# design.net
KiCad netlist of a schematic drawn in Altium Designer
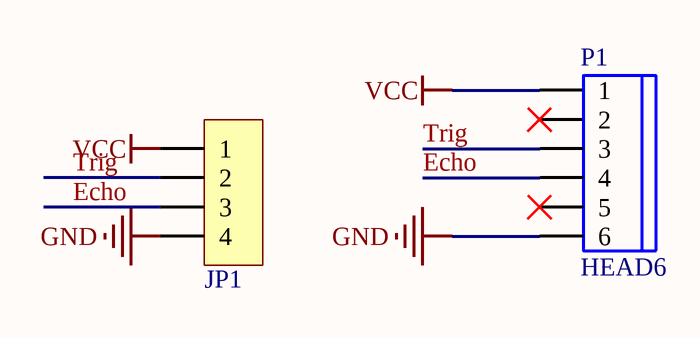
[diagram p0: 超声波模块云台原理图.SchDoc]

(export (version "E")
  (design (tool "Eeschema 10.0.6"))
  (components
    (comp (ref "JP1")
      (value "HDR-1X4")
      (footprint "HDR2.54-LI-4P")
      (description "4P接插件")
      (fields (field (name "版权归属") "封装库来自淘宝 ID：黄晶宝石"))
      (libsource (lib "5.3 - 接插件-脚距2.54 (100mil) ") (part "Header 4"))
    )
    (comp (ref "P1") (value "HEAD6") (footprint "SH1.0-6P") (libsource (lib "REMOTOR") (part "HEAD6")))
  )
  (nets
    (net (code "1") (name "/Echo") (class "Default")
      (node (ref "JP1") (pin "3") (pinfunction "3_3") (pintype "passive"))
      (node (ref "P1") (pin "4") (pinfunction "4_4") (pintype "passive"))
    )
    (net (code "2") (name "/Trig") (class "Default")
      (node (ref "JP1") (pin "2") (pinfunction "2_2") (pintype "passive"))
      (node (ref "P1") (pin "3") (pinfunction "3_3") (pintype "passive"))
    )
    (net (code "3") (name "GND") (class "Default")
      (node (ref "JP1") (pin "4") (pinfunction "4_4") (pintype "passive"))
      (node (ref "P1") (pin "6") (pinfunction "6_6") (pintype "passive"))
    )
    (net (code "4") (name "VCC") (class "Default")
      (node (ref "JP1") (pin "1") (pinfunction "1_1") (pintype "passive"))
      (node (ref "P1") (pin "1") (pinfunction "1_1") (pintype "passive"))
    )
    (net (code "5") (name "unconnected-(P1-Pad2)") (class "Default")
      (node (ref "P1") (pin "2") (pinfunction "2_2") (pintype "passive+no_connect"))
    )
    (net (code "6") (name "unconnected-(P1-Pad5)") (class "Default")
      (node (ref "P1") (pin "5") (pinfunction "5_5") (pintype "passive+no_connect"))
    )
  )
)
